# Reference_voltage.net
KiCad netlist of a schematic drawn in Altium Designer
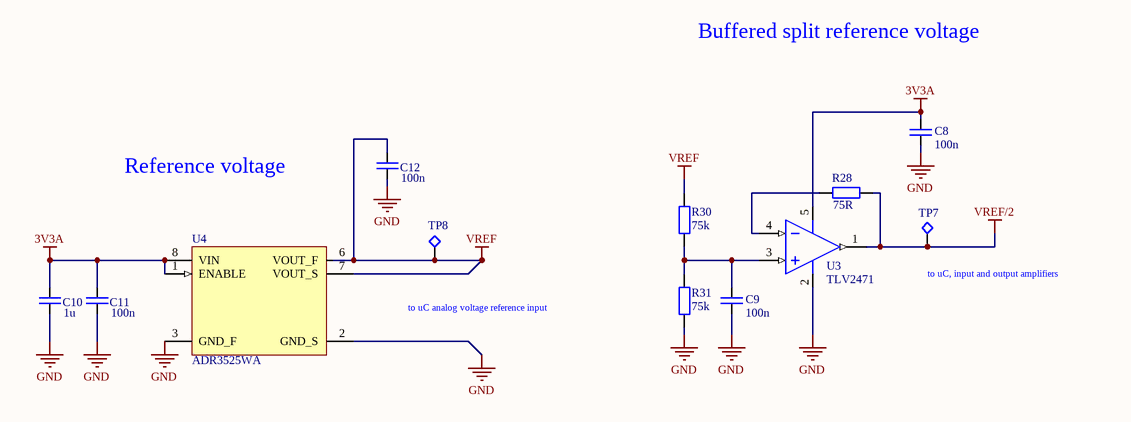
[diagram p0: Reference_voltage.SchDoc]

(export (version "E")
  (design (tool "Eeschema 10.0.6"))
  (components
    (comp (ref "C8")
      (value "100n")
      (footprint "C_0603")
      (description "Generic capacitor")
      (fields (field (name "Comment") "comment"))
      (libsource (lib "DAQ") (part "Capacitor"))
    )
    (comp (ref "C9")
      (value "100n")
      (footprint "C_0603")
      (description "Generic capacitor")
      (fields (field (name "Comment") "comment"))
      (libsource (lib "DAQ") (part "Capacitor"))
    )
    (comp (ref "C10")
      (value "1u")
      (footprint "C_0603")
      (description "Generic capacitor")
      (fields (field (name "Comment") "comment"))
      (libsource (lib "DAQ") (part "Capacitor"))
    )
    (comp (ref "C11")
      (value "100n")
      (footprint "C_0603")
      (description "Generic capacitor")
      (fields (field (name "Comment") "comment"))
      (libsource (lib "DAQ") (part "Capacitor"))
    )
    (comp (ref "C12")
      (value "100n")
      (footprint "C_0603")
      (description "Generic capacitor")
      (fields (field (name "Comment") "comment"))
      (libsource (lib "DAQ") (part "Capacitor"))
    )
    (comp (ref "R28")
      (value "75R")
      (footprint "R_0603")
      (description "Generic resistor")
      (fields (field (name "Comment") "comment"))
      (libsource (lib "DAQ") (part "Resistor"))
    )
    (comp (ref "R30")
      (value "75k")
      (footprint "R_0603")
      (description "Generic resistor")
      (fields (field (name "Comment") "comment"))
      (libsource (lib "DAQ") (part "Resistor"))
    )
    (comp (ref "R31")
      (value "75k")
      (footprint "R_0603")
      (description "Generic resistor")
      (fields (field (name "Comment") "comment"))
      (libsource (lib "DAQ") (part "Resistor"))
    )
    (comp (ref "TP7")
      (value "testpoint")
      (footprint "TP1_FULL")
      (description "testpoint 1.5mm diameter no hole")
      (fields (field (name "PART NUMBER") "XXC0006"))
      (libsource (lib "DAQ") (part "Test Point"))
    )
    (comp (ref "TP8")
      (value "testpoint")
      (footprint "TP1_FULL")
      (description "testpoint 1.5mm diameter no hole")
      (fields (field (name "PART NUMBER") "XXC0006"))
      (libsource (lib "DAQ") (part "Test Point"))
    )
    (comp (ref "U3")
      (value "TLV2471")
      (footprint "SOT23-5")
      (fields (field (name "PART NUMBER") "XOG0002") (field (name "MANUFACTURER") "Texas Instruments"))
      (libsource (lib "DAQ") (part "TLV2471"))
    )
    (comp (ref "U4")
      (value "ADR3525WA")
      (footprint "MSOP8")
      (description "Precision Voltage References 2.5V CMOS 8ppm/C")
      (fields (field (name "PART NUMBER") "VRX0002") (field (name "MANUFACTURER") "Analog devices"))
      (libsource (lib "DAQ") (part "ADR3525W"))
    )
  )
  (nets
    (net (code "1") (name "3V3A") (class "Default")
      (node (ref "C10") (pin "1") (pinfunction "1_1") (pintype "passive"))
      (node (ref "C11") (pin "1") (pinfunction "1_1") (pintype "passive"))
      (node (ref "C8") (pin "2") (pinfunction "2_2") (pintype "passive"))
      (node (ref "U3") (pin "5") (pinfunction "V+_5") (pintype "power_in"))
      (node (ref "U4") (pin "1") (pinfunction "ENABLE_1") (pintype "input"))
      (node (ref "U4") (pin "8") (pinfunction "VIN_8") (pintype "power_in"))
    )
    (net (code "2") (name "GND") (class "Default")
      (node (ref "C10") (pin "2") (pinfunction "2_2") (pintype "passive"))
      (node (ref "C11") (pin "2") (pinfunction "2_2") (pintype "passive"))
      (node (ref "C12") (pin "2") (pinfunction "2_2") (pintype "passive"))
      (node (ref "C8") (pin "1") (pinfunction "1_1") (pintype "passive"))
      (node (ref "C9") (pin "2") (pinfunction "2_2") (pintype "passive"))
      (node (ref "R31") (pin "1") (pintype "passive"))
      (node (ref "U3") (pin "2") (pinfunction "V-_2") (pintype "power_in"))
      (node (ref "U4") (pin "2") (pinfunction "GND_S_2") (pintype "power_in"))
      (node (ref "U4") (pin "3") (pinfunction "GND_F_3") (pintype "power_in"))
    )
    (net (code "3") (name "Net-(U3-+IN_A)") (class "Default")
      (node (ref "C9") (pin "1") (pinfunction "1_1") (pintype "passive"))
      (node (ref "R30") (pin "1") (pintype "passive"))
      (node (ref "R31") (pin "2") (pintype "passive"))
      (node (ref "U3") (pin "3") (pinfunction "+IN_A_3") (pintype "input"))
    )
    (net (code "4") (name "Net-(U3--IN_A)") (class "Default")
      (node (ref "R28") (pin "1") (pintype "passive"))
      (node (ref "U3") (pin "4") (pinfunction "-IN_A_4") (pintype "input"))
    )
    (net (code "5") (name "VREF") (class "Default")
      (node (ref "C12") (pin "1") (pinfunction "1_1") (pintype "passive"))
      (node (ref "R30") (pin "2") (pintype "passive"))
      (node (ref "TP8") (pin "1") (pinfunction "1_1") (pintype "passive"))
      (node (ref "U4") (pin "6") (pinfunction "VOUT_F_6") (pintype "power_in"))
      (node (ref "U4") (pin "7") (pinfunction "VOUT_S_7") (pintype "power_in"))
    )
    (net (code "6") (name "VREF{slash}2") (class "Default")
      (node (ref "R28") (pin "2") (pintype "passive"))
      (node (ref "TP7") (pin "1") (pinfunction "1_1") (pintype "passive"))
      (node (ref "U3") (pin "1") (pinfunction "OUT_A_1") (pintype "output"))
    )
  )
)
